# heart_eyes.net
KiCad netlist of a schematic drawn in EAGLE
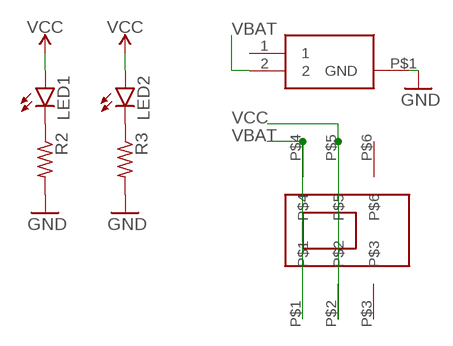
[diagram p0: schematic, sheet 1]

(export (version "E")
  (design (tool "Eeschema 10.0.6"))
  (components
    (comp (ref "LED1")
      (value "LEDCHIP-LED0805")
      (footprint "eagle-import:CHIP-LED0805")
      (libsource (lib "eagle-import") (part "LEDCHIP-LED0805"))
    )
    (comp (ref "LED2")
      (value "LEDCHIP-LED0805")
      (footprint "eagle-import:CHIP-LED0805")
      (libsource (lib "eagle-import") (part "LEDCHIP-LED0805"))
    )
    (comp (ref "R2")
      (value "R-US_R0603")
      (footprint "eagle-import:R0603")
      (libsource (lib "eagle-import") (part "R-US_R0603"))
    )
    (comp (ref "R3")
      (value "R-US_R0603")
      (footprint "eagle-import:R0603")
      (libsource (lib "eagle-import") (part "R-US_R0603"))
    )
    (comp (ref "U$1")
      (value "CL-SB-22A-02T-SLIDE-SWITCH-TUCKED-PADS")
      (footprint "eagle-import:CL-SB-22A-02T-DPDT-COMPACT-SWITCH")
      (libsource (lib "eagle-import") (part "CL-SB-22A-02T-SLIDE-SWITCH-TUCKED-PADS"))
    )
    (comp (ref "VBAT")
      (value "BAT-HLD-012-SMT")
      (footprint "eagle-import:BATHLD012SMT")
      (fields (field (name "MOUSER_PART_NUMBER") "712-BAT-HLD-012-SMT"))
      (libsource (lib "eagle-import") (part "BAT-HLD-012-SMT"))
    )
  )
  (nets
    (net (code "1") (name "/VBAT") (class "Default")
      (node (ref "U$1") (pin "P$1") (pinfunction "P$1_P$1") (pintype "bidirectional"))
      (node (ref "U$1") (pin "P$4") (pinfunction "P$4_P$4") (pintype "bidirectional"))
      (node (ref "VBAT") (pin "2") (pinfunction "2_2") (pintype "bidirectional"))
    )
    (net (code "2") (name "GND") (class "Default")
      (node (ref "R2") (pin "2") (pinfunction "2_2") (pintype "passive"))
      (node (ref "R3") (pin "2") (pinfunction "2_2") (pintype "passive"))
      (node (ref "VBAT") (pin "P$1") (pinfunction "GND_P$1") (pintype "bidirectional"))
    )
    (net (code "3") (name "Net-(LED1-PadC)") (class "Default")
      (node (ref "LED1") (pin "C") (pinfunction "C_C") (pintype "passive"))
      (node (ref "R2") (pin "1") (pinfunction "1_1") (pintype "passive"))
    )
    (net (code "4") (name "Net-(LED2-PadC)") (class "Default")
      (node (ref "LED2") (pin "C") (pinfunction "C_C") (pintype "passive"))
      (node (ref "R3") (pin "1") (pinfunction "1_1") (pintype "passive"))
    )
    (net (code "5") (name "VCC") (class "Default")
      (node (ref "LED1") (pin "A") (pinfunction "A_A") (pintype "passive"))
      (node (ref "LED2") (pin "A") (pinfunction "A_A") (pintype "passive"))
      (node (ref "U$1") (pin "P$2") (pinfunction "P$2_P$2") (pintype "bidirectional"))
      (node (ref "U$1") (pin "P$5") (pinfunction "P$5_P$5") (pintype "bidirectional"))
    )
    (net (code "6") (name "unconnected-(U$1-PadP$3)") (class "Default")
      (node (ref "U$1") (pin "P$3") (pinfunction "P$3_P$3") (pintype "bidirectional"))
    )
    (net (code "7") (name "unconnected-(U$1-PadP$6)") (class "Default")
      (node (ref "U$1") (pin "P$6") (pinfunction "P$6_P$6") (pintype "bidirectional"))
    )
    (net (code "8") (name "unconnected-(VBAT-Pad1)") (class "Default")
      (node (ref "VBAT") (pin "1") (pinfunction "1_1") (pintype "bidirectional"))
    )
  )
)
